# PWR_Sensor_Input.net
KiCad netlist of a schematic drawn in Altium Designer
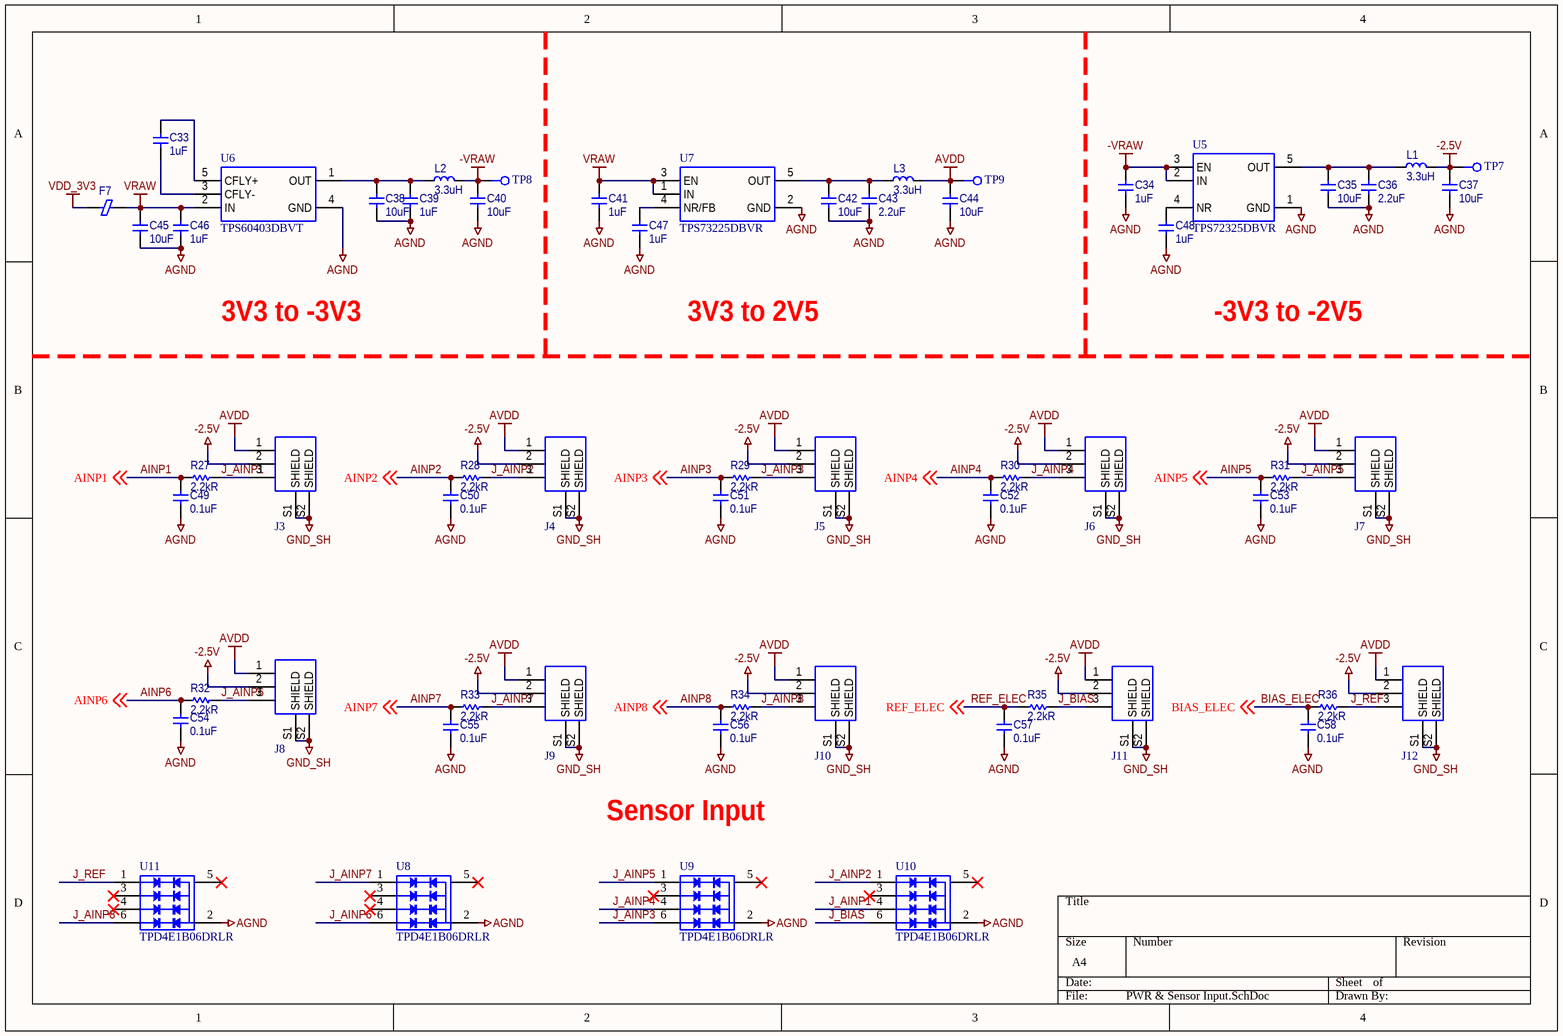
[diagram p0: PWR & Sensor Input.SchDoc]

(export (version "E")
  (design (tool "Eeschema 10.0.6"))
  (components
    (comp (ref "C33")
      (value "1uF")
      (footprint "C1005X04N")
      (description "CAP CER,1UF,10%,16V,X5R,0402,SMD")
      (fields
        (field (name "MANUFACTURER PART NUMBER") "EMK105BJ105KV-F")
        (field (name "MANUFACTURER") "Taiyo Yuden")
      )
      (libsource (lib "Database Library") (part "C_CAPN"))
    )
    (comp (ref "C34")
      (value "1uF")
      (footprint "C1005X04N")
      (description "CAP CER,1UF,10%,16V,X5R,0402,SMD")
      (fields
        (field (name "MANUFACTURER PART NUMBER") "EMK105BJ105KV-F")
        (field (name "MANUFACTURER") "Taiyo Yuden")
      )
      (libsource (lib "Database Library") (part "C_CAPN"))
    )
    (comp (ref "C35")
      (value "10uF")
      (footprint "C1608X06N")
      (description "CAP CER,10UF,20%,10V,X5R,0603,SMD")
      (fields
        (field (name "MANUFACTURER PART NUMBER") "LMK107BBJ106MAHT")
        (field (name "MANUFACTURER") "Taiyo Yuden")
      )
      (libsource (lib "Database Library") (part "C_CAPN"))
    )
    (comp (ref "C36")
      (value "2.2uF")
      (footprint "C1005X04N")
      (description "CAP CER,2.2UF,20%,25V,X5R,0402,SMD")
      (fields
        (field (name "MANUFACTURER PART NUMBER") "TMK105CBJ225MV-F")
        (field (name "MANUFACTURER") "Taiyo Yuden")
      )
      (libsource (lib "Database Library") (part "C_CAPN"))
    )
    (comp (ref "C37")
      (value "10uF")
      (footprint "C1608X06N")
      (description "CAP CER,10UF,20%,10V,X5R,0603,SMD")
      (fields
        (field (name "MANUFACTURER PART NUMBER") "LMK107BBJ106MAHT")
        (field (name "MANUFACTURER") "Taiyo Yuden")
      )
      (libsource (lib "Database Library") (part "C_CAPN"))
    )
    (comp (ref "C38")
      (value "10uF")
      (footprint "C1608X06N")
      (description "CAP CER,10UF,20%,10V,X5R,0603,SMD")
      (fields
        (field (name "MANUFACTURER PART NUMBER") "LMK107BBJ106MAHT")
        (field (name "MANUFACTURER") "Taiyo Yuden")
      )
      (libsource (lib "Database Library") (part "C_CAPN"))
    )
    (comp (ref "C39")
      (value "1uF")
      (footprint "C1005X04N")
      (description "CAP CER,1UF,10%,16V,X5R,0402,SMD")
      (fields
        (field (name "MANUFACTURER PART NUMBER") "EMK105BJ105KV-F")
        (field (name "MANUFACTURER") "Taiyo Yuden")
      )
      (libsource (lib "Database Library") (part "C_CAPN"))
    )
    (comp (ref "C40")
      (value "10uF")
      (footprint "C1608X06N")
      (description "CAP CER,10UF,20%,10V,X5R,0603,SMD")
      (fields
        (field (name "MANUFACTURER PART NUMBER") "LMK107BBJ106MAHT")
        (field (name "MANUFACTURER") "Taiyo Yuden")
      )
      (libsource (lib "Database Library") (part "C_CAPN"))
    )
    (comp (ref "C41")
      (value "1uF")
      (footprint "C1005X04N")
      (description "CAP CER,1UF,10%,16V,X5R,0402,SMD")
      (fields
        (field (name "MANUFACTURER PART NUMBER") "EMK105BJ105KV-F")
        (field (name "MANUFACTURER") "Taiyo Yuden")
      )
      (libsource (lib "Database Library") (part "C_CAPN"))
    )
    (comp (ref "C42")
      (value "10uF")
      (footprint "C1608X06N")
      (description "CAP CER,10UF,20%,10V,X5R,0603,SMD")
      (fields
        (field (name "MANUFACTURER PART NUMBER") "LMK107BBJ106MAHT")
        (field (name "MANUFACTURER") "Taiyo Yuden")
      )
      (libsource (lib "Database Library") (part "C_CAPN"))
    )
    (comp (ref "C43")
      (value "2.2uF")
      (footprint "C1005X04N")
      (description "CAP CER,2.2UF,20%,25V,X5R,0402,SMD")
      (fields
        (field (name "MANUFACTURER PART NUMBER") "TMK105CBJ225MV-F")
        (field (name "MANUFACTURER") "Taiyo Yuden")
      )
      (libsource (lib "Database Library") (part "C_CAPN"))
    )
    (comp (ref "C44")
      (value "10uF")
      (footprint "C1608X06N")
      (description "CAP CER,10UF,20%,10V,X5R,0603,SMD")
      (fields
        (field (name "MANUFACTURER PART NUMBER") "LMK107BBJ106MAHT")
        (field (name "MANUFACTURER") "Taiyo Yuden")
      )
      (libsource (lib "Database Library") (part "C_CAPN"))
    )
    (comp (ref "C45")
      (value "10uF")
      (footprint "C1608X06N")
      (description "CAP CER,10UF,20%,10V,X5R,0603,SMD")
      (fields
        (field (name "MANUFACTURER PART NUMBER") "LMK107BBJ106MAHT")
        (field (name "MANUFACTURER") "Taiyo Yuden")
      )
      (libsource (lib "Database Library") (part "C_CAPN"))
    )
    (comp (ref "C46")
      (value "1uF")
      (footprint "C1005X04N")
      (description "CAP CER,1UF,10%,16V,X5R,0402,SMD")
      (fields
        (field (name "MANUFACTURER PART NUMBER") "EMK105BJ105KV-F")
        (field (name "MANUFACTURER") "Taiyo Yuden")
      )
      (libsource (lib "Database Library") (part "C_CAPN"))
    )
    (comp (ref "C47")
      (value "1uF")
      (footprint "C1005X04N")
      (description "CAP CER,1UF,10%,16V,X5R,0402,SMD")
      (fields
        (field (name "MANUFACTURER PART NUMBER") "EMK105BJ105KV-F")
        (field (name "MANUFACTURER") "Taiyo Yuden")
      )
      (libsource (lib "Database Library") (part "C_CAPN"))
    )
    (comp (ref "C48")
      (value "1uF")
      (footprint "C1005X04N")
      (description "CAP CER,1UF,10%,16V,X5R,0402,SMD")
      (fields
        (field (name "MANUFACTURER PART NUMBER") "EMK105BJ105KV-F")
        (field (name "MANUFACTURER") "Taiyo Yuden")
      )
      (libsource (lib "Database Library") (part "C_CAPN"))
    )
    (comp (ref "C49")
      (value "0.1uF")
      (footprint "C1005X04N")
      (description "CAP CER,0.1UF,20%,25V,X5R,0402,SMD")
      (fields
        (field (name "MANUFACTURER PART NUMBER") "TMK105BJ104MV-F")
        (field (name "MANUFACTURER") "Taiyo Yuden")
      )
      (libsource (lib "Database Library") (part "C_CAPN"))
    )
    (comp (ref "C50")
      (value "0.1uF")
      (footprint "C1005X04N")
      (description "CAP CER,0.1UF,20%,25V,X5R,0402,SMD")
      (fields
        (field (name "MANUFACTURER PART NUMBER") "TMK105BJ104MV-F")
        (field (name "MANUFACTURER") "Taiyo Yuden")
      )
      (libsource (lib "Database Library") (part "C_CAPN"))
    )
    (comp (ref "C51")
      (value "0.1uF")
      (footprint "C1005X04N")
      (description "CAP CER,0.1UF,20%,25V,X5R,0402,SMD")
      (fields
        (field (name "MANUFACTURER PART NUMBER") "TMK105BJ104MV-F")
        (field (name "MANUFACTURER") "Taiyo Yuden")
      )
      (libsource (lib "Database Library") (part "C_CAPN"))
    )
    (comp (ref "C52")
      (value "0.1uF")
      (footprint "C1005X04N")
      (description "CAP CER,0.1UF,20%,25V,X5R,0402,SMD")
      (fields
        (field (name "MANUFACTURER PART NUMBER") "TMK105BJ104MV-F")
        (field (name "MANUFACTURER") "Taiyo Yuden")
      )
      (libsource (lib "Database Library") (part "C_CAPN"))
    )
    (comp (ref "C53")
      (value "0.1uF")
      (footprint "C1005X04N")
      (description "CAP CER,0.1UF,20%,25V,X5R,0402,SMD")
      (fields
        (field (name "MANUFACTURER PART NUMBER") "TMK105BJ104MV-F")
        (field (name "MANUFACTURER") "Taiyo Yuden")
      )
      (libsource (lib "Database Library") (part "C_CAPN"))
    )
    (comp (ref "C54")
      (value "0.1uF")
      (footprint "C1005X04N")
      (description "CAP CER,0.1UF,20%,25V,X5R,0402,SMD")
      (fields
        (field (name "MANUFACTURER PART NUMBER") "TMK105BJ104MV-F")
        (field (name "MANUFACTURER") "Taiyo Yuden")
      )
      (libsource (lib "Database Library") (part "C_CAPN"))
    )
    (comp (ref "C55")
      (value "0.1uF")
      (footprint "C1005X04N")
      (description "CAP CER,0.1UF,20%,25V,X5R,0402,SMD")
      (fields
        (field (name "MANUFACTURER PART NUMBER") "TMK105BJ104MV-F")
        (field (name "MANUFACTURER") "Taiyo Yuden")
      )
      (libsource (lib "Database Library") (part "C_CAPN"))
    )
    (comp (ref "C56")
      (value "0.1uF")
      (footprint "C1005X04N")
      (description "CAP CER,0.1UF,20%,25V,X5R,0402,SMD")
      (fields
        (field (name "MANUFACTURER PART NUMBER") "TMK105BJ104MV-F")
        (field (name "MANUFACTURER") "Taiyo Yuden")
      )
      (libsource (lib "Database Library") (part "C_CAPN"))
    )
    (comp (ref "C57")
      (value "0.1uF")
      (footprint "C1005X04N")
      (description "CAP CER,0.1UF,20%,25V,X5R,0402,SMD")
      (fields
        (field (name "MANUFACTURER PART NUMBER") "TMK105BJ104MV-F")
        (field (name "MANUFACTURER") "Taiyo Yuden")
      )
      (libsource (lib "Database Library") (part "C_CAPN"))
    )
    (comp (ref "C58")
      (value "0.1uF")
      (footprint "C1005X04N")
      (description "CAP CER,0.1UF,20%,25V,X5R,0402,SMD")
      (fields
        (field (name "MANUFACTURER PART NUMBER") "TMK105BJ104MV-F")
        (field (name "MANUFACTURER") "Taiyo Yuden")
      )
      (libsource (lib "Database Library") (part "C_CAPN"))
    )
    (comp (ref "F7")
      (value "120 Ohms @ 100MHz")
      (footprint "F3216X07N")
      (description "FERRITE BEAD,120 OHMS @ 100MHZ,0.0016R,3A,1206,SMD")
      (fields
        (field (name "MANUFACTURER PART NUMBER") "BLM31KN271BH1L")
        (field (name "MANUFACTURER") "Murata Electronics")
      )
      (libsource (lib "Database Library") (part "F_FERRITE_BEAD"))
    )
    (comp (ref "J3")
      (value "SM03B-SRSS-TB(LF)(SN)")
      (footprint "JST_SM03B-SRSS-TB(LF)(SN)")
      (description "CONN HEADER SMD R/A 3POS 1MM")
      (fields (field (name "MANUFACTURER") "JST Sales America Inc."))
      (libsource (lib "DungMV") (part "SM03B-SRSS-TB(LF)(SN)"))
    )
    (comp (ref "J4")
      (value "SM03B-SRSS-TB(LF)(SN)")
      (footprint "JST_SM03B-SRSS-TB(LF)(SN)")
      (description "CONN HEADER SMD R/A 3POS 1MM")
      (fields (field (name "MANUFACTURER") "JST Sales America Inc."))
      (libsource (lib "DungMV") (part "SM03B-SRSS-TB(LF)(SN)"))
    )
    (comp (ref "J5")
      (value "SM03B-SRSS-TB(LF)(SN)")
      (footprint "JST_SM03B-SRSS-TB(LF)(SN)")
      (description "CONN HEADER SMD R/A 3POS 1MM")
      (fields (field (name "MANUFACTURER") "JST Sales America Inc."))
      (libsource (lib "DungMV") (part "SM03B-SRSS-TB(LF)(SN)"))
    )
    (comp (ref "J6")
      (value "SM03B-SRSS-TB(LF)(SN)")
      (footprint "JST_SM03B-SRSS-TB(LF)(SN)")
      (description "CONN HEADER SMD R/A 3POS 1MM")
      (fields (field (name "MANUFACTURER") "JST Sales America Inc."))
      (libsource (lib "DungMV") (part "SM03B-SRSS-TB(LF)(SN)"))
    )
    (comp (ref "J7")
      (value "SM03B-SRSS-TB(LF)(SN)")
      (footprint "JST_SM03B-SRSS-TB(LF)(SN)")
      (description "CONN HEADER SMD R/A 3POS 1MM")
      (fields (field (name "MANUFACTURER") "JST Sales America Inc."))
      (libsource (lib "DungMV") (part "SM03B-SRSS-TB(LF)(SN)"))
    )
    (comp (ref "J8")
      (value "SM03B-SRSS-TB(LF)(SN)")
      (footprint "JST_SM03B-SRSS-TB(LF)(SN)")
      (description "CONN HEADER SMD R/A 3POS 1MM")
      (fields (field (name "MANUFACTURER") "JST Sales America Inc."))
      (libsource (lib "DungMV") (part "SM03B-SRSS-TB(LF)(SN)"))
    )
    (comp (ref "J9")
      (value "SM03B-SRSS-TB(LF)(SN)")
      (footprint "JST_SM03B-SRSS-TB(LF)(SN)")
      (description "CONN HEADER SMD R/A 3POS 1MM")
      (fields (field (name "MANUFACTURER") "JST Sales America Inc."))
      (libsource (lib "DungMV") (part "SM03B-SRSS-TB(LF)(SN)"))
    )
    (comp (ref "J10")
      (value "SM03B-SRSS-TB(LF)(SN)")
      (footprint "JST_SM03B-SRSS-TB(LF)(SN)")
      (description "CONN HEADER SMD R/A 3POS 1MM")
      (fields (field (name "MANUFACTURER") "JST Sales America Inc."))
      (libsource (lib "DungMV") (part "SM03B-SRSS-TB(LF)(SN)"))
    )
    (comp (ref "J11")
      (value "SM03B-SRSS-TB(LF)(SN)")
      (footprint "JST_SM03B-SRSS-TB(LF)(SN)")
      (description "CONN HEADER SMD R/A 3POS 1MM")
      (fields (field (name "MANUFACTURER") "JST Sales America Inc."))
      (libsource (lib "DungMV") (part "SM03B-SRSS-TB(LF)(SN)"))
    )
    (comp (ref "J12")
      (value "SM03B-SRSS-TB(LF)(SN)")
      (footprint "JST_SM03B-SRSS-TB(LF)(SN)")
      (description "CONN HEADER SMD R/A 3POS 1MM")
      (fields (field (name "MANUFACTURER") "JST Sales America Inc."))
      (libsource (lib "DungMV") (part "SM03B-SRSS-TB(LF)(SN)"))
    )
    (comp (ref "L1")
      (value "3.3uH")
      (footprint "L1608X06N")
      (description "IND,3.3UH,20%,450MA,0.027R,0603,SMD")
      (fields
        (field (name "MANUFACTURER PART NUMBER") "MLZ1608N3R3LT000")
        (field (name "MANUFACTURER") "TDK Corporation")
      )
      (libsource (lib "Database Library") (part "L_IND_AIR"))
    )
    (comp (ref "L2")
      (value "3.3uH")
      (footprint "L1608X06N")
      (description "IND,3.3UH,20%,450MA,0.027R,0603,SMD")
      (fields
        (field (name "MANUFACTURER PART NUMBER") "MLZ1608N3R3LT000")
        (field (name "MANUFACTURER") "TDK Corporation")
      )
      (libsource (lib "Database Library") (part "L_IND_AIR"))
    )
    (comp (ref "L3")
      (value "3.3uH")
      (footprint "L1608X06N")
      (description "IND,3.3UH,20%,450MA,0.027R,0603,SMD")
      (fields
        (field (name "MANUFACTURER PART NUMBER") "MLZ1608N3R3LT000")
        (field (name "MANUFACTURER") "TDK Corporation")
      )
      (libsource (lib "Database Library") (part "L_IND_AIR"))
    )
    (comp (ref "R27")
      (value "2.2kR")
      (footprint "R1005X04N")
      (description "RES,2.2KR,1%,62.5MW,0402,SMD")
      (fields
        (field (name "MANUFACTURER PART NUMBER") "RC0402FR-072K2L")
        (field (name "MANUFACTURER") "Yageo")
      )
      (libsource (lib "Database Library") (part "R_RES"))
    )
    (comp (ref "R28")
      (value "2.2kR")
      (footprint "R1005X04N")
      (description "RES,2.2KR,1%,62.5MW,0402,SMD")
      (fields
        (field (name "MANUFACTURER PART NUMBER") "RC0402FR-072K2L")
        (field (name "MANUFACTURER") "Yageo")
      )
      (libsource (lib "Database Library") (part "R_RES"))
    )
    (comp (ref "R29")
      (value "2.2kR")
      (footprint "R1005X04N")
      (description "RES,2.2KR,1%,62.5MW,0402,SMD")
      (fields
        (field (name "MANUFACTURER PART NUMBER") "RC0402FR-072K2L")
        (field (name "MANUFACTURER") "Yageo")
      )
      (libsource (lib "Database Library") (part "R_RES"))
    )
    (comp (ref "R30")
      (value "2.2kR")
      (footprint "R1005X04N")
      (description "RES,2.2KR,1%,62.5MW,0402,SMD")
      (fields
        (field (name "MANUFACTURER PART NUMBER") "RC0402FR-072K2L")
        (field (name "MANUFACTURER") "Yageo")
      )
      (libsource (lib "Database Library") (part "R_RES"))
    )
    (comp (ref "R31")
      (value "2.2kR")
      (footprint "R1005X04N")
      (description "RES,2.2KR,1%,62.5MW,0402,SMD")
      (fields
        (field (name "MANUFACTURER PART NUMBER") "RC0402FR-072K2L")
        (field (name "MANUFACTURER") "Yageo")
      )
      (libsource (lib "Database Library") (part "R_RES"))
    )
    (comp (ref "R32")
      (value "2.2kR")
      (footprint "R1005X04N")
      (description "RES,2.2KR,1%,62.5MW,0402,SMD")
      (fields
        (field (name "MANUFACTURER PART NUMBER") "RC0402FR-072K2L")
        (field (name "MANUFACTURER") "Yageo")
      )
      (libsource (lib "Database Library") (part "R_RES"))
    )
    (comp (ref "R33")
      (value "2.2kR")
      (footprint "R1005X04N")
      (description "RES,2.2KR,1%,62.5MW,0402,SMD")
      (fields
        (field (name "MANUFACTURER PART NUMBER") "RC0402FR-072K2L")
        (field (name "MANUFACTURER") "Yageo")
      )
      (libsource (lib "Database Library") (part "R_RES"))
    )
    (comp (ref "R34")
      (value "2.2kR")
      (footprint "R1005X04N")
      (description "RES,2.2KR,1%,62.5MW,0402,SMD")
      (fields
        (field (name "MANUFACTURER PART NUMBER") "RC0402FR-072K2L")
        (field (name "MANUFACTURER") "Yageo")
      )
      (libsource (lib "Database Library") (part "R_RES"))
    )
    (comp (ref "R35")
      (value "2.2kR")
      (footprint "R1005X04N")
      (description "RES,2.2KR,1%,62.5MW,0402,SMD")
      (fields
        (field (name "MANUFACTURER PART NUMBER") "RC0402FR-072K2L")
        (field (name "MANUFACTURER") "Yageo")
      )
      (libsource (lib "Database Library") (part "R_RES"))
    )
    (comp (ref "R36")
      (value "2.2kR")
      (footprint "R1005X04N")
      (description "RES,2.2KR,1%,62.5MW,0402,SMD")
      (fields
        (field (name "MANUFACTURER PART NUMBER") "RC0402FR-072K2L")
        (field (name "MANUFACTURER") "Yageo")
      )
      (libsource (lib "Database Library") (part "R_RES"))
    )
    (comp (ref "TP7")
      (value "TP_25MILC")
      (footprint "TESTPOINT_1MM")
      (description "Test Point 25mil")
      (libsource (lib "DungMV") (part "TP_25MILC"))
    )
    (comp (ref "TP8")
      (value "TP_25MILC")
      (footprint "TESTPOINT_1MM")
      (description "Test Point 25mil")
      (libsource (lib "DungMV") (part "TP_25MILC"))
    )
    (comp (ref "TP9")
      (value "TP_25MILC")
      (footprint "TESTPOINT_1MM")
      (description "Test Point 25mil")
      (libsource (lib "DungMV") (part "TP_25MILC"))
    )
    (comp (ref "U5")
      (value "TPS72325DBVR")
      (footprint "SOT23-5")
      (description "IC REG LIN -2.5V 200MA SOT23-5")
      (fields (field (name "MANUFACTURER") "Texas Instruments"))
      (libsource (lib "DungMV") (part "TPS72325DBVR"))
    )
    (comp (ref "U6")
      (value "TPS60403DBVT")
      (footprint "SOT23-5")
      (description "TPS60403 60MA CHARGE PUMP VOLTAG")
      (fields (field (name "MANUFACTURER") "Texas Instruments"))
      (libsource (lib "DungMV") (part "TPS60403DBVT"))
    )
    (comp (ref "U7")
      (value "TPS73225DBVR")
      (footprint "SOT23-5")
      (description "IC REG LINEAR 2.5V 250MA SOT23-5")
      (fields (field (name "MANUFACTURER") "Texas Instruments"))
      (libsource (lib "DungMV") (part "TPS73225DBVR"))
    )
    (comp (ref "U8")
      (value "TPD4E1B06DRLR")
      (footprint "SOT-563")
      (description "TVS DIODE 5.5VWM 14.5VC 6SOT")
      (fields (field (name "MANUFACTURER") "Texas Instruments"))
      (libsource (lib "DungMV") (part "TPD4E1B06DRLR"))
    )
    (comp (ref "U9")
      (value "TPD4E1B06DRLR")
      (footprint "SOT-563")
      (description "TVS DIODE 5.5VWM 14.5VC 6SOT")
      (fields (field (name "MANUFACTURER") "Texas Instruments"))
      (libsource (lib "DungMV") (part "TPD4E1B06DRLR"))
    )
    (comp (ref "U10")
      (value "TPD4E1B06DRLR")
      (footprint "SOT-563")
      (description "TVS DIODE 5.5VWM 14.5VC 6SOT")
      (fields (field (name "MANUFACTURER") "Texas Instruments"))
      (libsource (lib "DungMV") (part "TPD4E1B06DRLR"))
    )
    (comp (ref "U11")
      (value "TPD4E1B06DRLR")
      (footprint "SOT-563")
      (description "TVS DIODE 5.5VWM 14.5VC 6SOT")
      (fields (field (name "MANUFACTURER") "Texas Instruments"))
      (libsource (lib "DungMV") (part "TPD4E1B06DRLR"))
    )
  )
  (nets
    (net (code "1") (name "-2.5V") (class "Default")
      (node (ref "C37") (pin "2") (pinfunction "2_2") (pintype "passive"))
      (node (ref "J10") (pin "2") (pinfunction "2_2") (pintype "passive"))
      (node (ref "J11") (pin "2") (pinfunction "2_2") (pintype "passive"))
      (node (ref "J12") (pin "2") (pinfunction "2_2") (pintype "passive"))
      (node (ref "J3") (pin "2") (pinfunction "2_2") (pintype "passive"))
      (node (ref "J4") (pin "2") (pinfunction "2_2") (pintype "passive"))
      (node (ref "J5") (pin "2") (pinfunction "2_2") (pintype "passive"))
      (node (ref "J6") (pin "2") (pinfunction "2_2") (pintype "passive"))
      (node (ref "J7") (pin "2") (pinfunction "2_2") (pintype "passive"))
      (node (ref "J8") (pin "2") (pinfunction "2_2") (pintype "passive"))
      (node (ref "J9") (pin "2") (pinfunction "2_2") (pintype "passive"))
      (node (ref "L1") (pin "2") (pinfunction "2_2") (pintype "passive"))
      (node (ref "TP7") (pin "1") (pinfunction "1_1") (pintype "passive"))
    )
    (net (code "2") (name "-VRAW") (class "Default")
      (node (ref "C34") (pin "1") (pinfunction "1_1") (pintype "passive"))
      (node (ref "C40") (pin "2") (pinfunction "2_2") (pintype "passive"))
      (node (ref "L2") (pin "2") (pinfunction "2_2") (pintype "passive"))
      (node (ref "TP8") (pin "1") (pinfunction "1_1") (pintype "passive"))
      (node (ref "U5") (pin "2") (pinfunction "IN_2") (pintype "passive"))
      (node (ref "U5") (pin "3") (pinfunction "EN_3") (pintype "passive"))
    )
    (net (code "3") (name "/J_AINP1") (class "Default")
      (node (ref "J3") (pin "3") (pinfunction "3_3") (pintype "passive"))
      (node (ref "R27") (pin "2") (pinfunction "2_2") (pintype "passive"))
      (node (ref "U10") (pin "4") (pinfunction "IO3_4") (pintype "passive"))
    )
    (net (code "4") (name "/J_AINP2") (class "Default")
      (node (ref "J4") (pin "3") (pinfunction "3_3") (pintype "passive"))
      (node (ref "R28") (pin "2") (pinfunction "2_2") (pintype "passive"))
      (node (ref "U10") (pin "1") (pinfunction "IO1_1") (pintype "passive"))
    )
    (net (code "5") (name "/J_AINP3") (class "Default")
      (node (ref "J5") (pin "3") (pinfunction "3_3") (pintype "passive"))
      (node (ref "R29") (pin "2") (pinfunction "2_2") (pintype "passive"))
      (node (ref "U9") (pin "6") (pinfunction "IO4_6") (pintype "power_in"))
    )
    (net (code "6") (name "/J_AINP4") (class "Default")
      (node (ref "J6") (pin "3") (pinfunction "3_3") (pintype "passive"))
      (node (ref "R30") (pin "2") (pinfunction "2_2") (pintype "passive"))
      (node (ref "U9") (pin "4") (pinfunction "IO3_4") (pintype "passive"))
    )
    (net (code "7") (name "/J_AINP5") (class "Default")
      (node (ref "J7") (pin "3") (pinfunction "3_3") (pintype "passive"))
      (node (ref "R31") (pin "2") (pinfunction "2_2") (pintype "passive"))
      (node (ref "U9") (pin "1") (pinfunction "IO1_1") (pintype "passive"))
    )
    (net (code "8") (name "/J_AINP6") (class "Default")
      (node (ref "J8") (pin "3") (pinfunction "3_3") (pintype "passive"))
      (node (ref "R32") (pin "2") (pinfunction "2_2") (pintype "passive"))
      (node (ref "U8") (pin "6") (pinfunction "IO4_6") (pintype "power_in"))
    )
    (net (code "9") (name "/J_AINP7") (class "Default")
      (node (ref "J9") (pin "3") (pinfunction "3_3") (pintype "passive"))
      (node (ref "R33") (pin "2") (pinfunction "2_2") (pintype "passive"))
      (node (ref "U8") (pin "1") (pinfunction "IO1_1") (pintype "passive"))
    )
    (net (code "10") (name "/J_AINP8") (class "Default")
      (node (ref "J10") (pin "3") (pinfunction "3_3") (pintype "passive"))
      (node (ref "R34") (pin "2") (pinfunction "2_2") (pintype "passive"))
      (node (ref "U11") (pin "6") (pinfunction "IO4_6") (pintype "power_in"))
    )
    (net (code "11") (name "/J_BIAS") (class "Default")
      (node (ref "J11") (pin "3") (pinfunction "3_3") (pintype "passive"))
      (node (ref "R35") (pin "2") (pinfunction "2_2") (pintype "passive"))
      (node (ref "U10") (pin "6") (pinfunction "IO4_6") (pintype "power_in"))
    )
    (net (code "12") (name "/J_REF") (class "Default")
      (node (ref "J12") (pin "3") (pinfunction "3_3") (pintype "passive"))
      (node (ref "R36") (pin "2") (pinfunction "2_2") (pintype "passive"))
      (node (ref "U11") (pin "1") (pinfunction "IO1_1") (pintype "passive"))
    )
    (net (code "13") (name "AGND") (class "Default")
      (node (ref "C34") (pin "2") (pinfunction "2_2") (pintype "passive"))
      (node (ref "C35") (pin "1") (pinfunction "1_1") (pintype "passive"))
      (node (ref "C36") (pin "1") (pinfunction "1_1") (pintype "passive"))
      (node (ref "C37") (pin "1") (pinfunction "1_1") (pintype "passive"))
      (node (ref "C38") (pin "1") (pinfunction "1_1") (pintype "passive"))
      (node (ref "C39") (pin "2") (pinfunction "2_2") (pintype "passive"))
      (node (ref "C40") (pin "1") (pinfunction "1_1") (pintype "passive"))
      (node (ref "C41") (pin "2") (pinfunction "2_2") (pintype "passive"))
      (node (ref "C42") (pin "1") (pinfunction "1_1") (pintype "passive"))
      (node (ref "C43") (pin "1") (pinfunction "1_1") (pintype "passive"))
      (node (ref "C44") (pin "1") (pinfunction "1_1") (pintype "passive"))
      (node (ref "C45") (pin "1") (pinfunction "1_1") (pintype "passive"))
      (node (ref "C46") (pin "2") (pinfunction "2_2") (pintype "passive"))
      (node (ref "C47") (pin "2") (pinfunction "2_2") (pintype "passive"))
      (node (ref "C48") (pin "2") (pinfunction "2_2") (pintype "passive"))
      (node (ref "C49") (pin "1") (pinfunction "1_1") (pintype "passive"))
      (node (ref "C50") (pin "1") (pinfunction "1_1") (pintype "passive"))
      (node (ref "C51") (pin "1") (pinfunction "1_1") (pintype "passive"))
      (node (ref "C52") (pin "1") (pinfunction "1_1") (pintype "passive"))
      (node (ref "C53") (pin "1") (pinfunction "1_1") (pintype "passive"))
      (node (ref "C54") (pin "1") (pinfunction "1_1") (pintype "passive"))
      (node (ref "C55") (pin "1") (pinfunction "1_1") (pintype "passive"))
      (node (ref "C56") (pin "1") (pinfunction "1_1") (pintype "passive"))
      (node (ref "C57") (pin "1") (pinfunction "1_1") (pintype "passive"))
      (node (ref "C58") (pin "1") (pinfunction "1_1") (pintype "passive"))
      (node (ref "U10") (pin "2") (pinfunction "GND_2") (pintype "passive"))
      (node (ref "U11") (pin "2") (pinfunction "GND_2") (pintype "passive"))
      (node (ref "U5") (pin "1") (pinfunction "GND_1") (pintype "passive"))
      (node (ref "U6") (pin "4") (pinfunction "GND_4") (pintype "passive"))
      (node (ref "U7") (pin "2") (pinfunction "GND_2") (pintype "passive"))
      (node (ref "U8") (pin "2") (pinfunction "GND_2") (pintype "passive"))
      (node (ref "U9") (pin "2") (pinfunction "GND_2") (pintype "passive"))
    )
    (net (code "14") (name "AINP1") (class "Default")
      (node (ref "C49") (pin "2") (pinfunction "2_2") (pintype "passive"))
      (node (ref "R27") (pin "1") (pinfunction "1_1") (pintype "passive"))
    )
    (net (code "15") (name "AINP2") (class "Default")
      (node (ref "C50") (pin "2") (pinfunction "2_2") (pintype "passive"))
      (node (ref "R28") (pin "1") (pinfunction "1_1") (pintype "passive"))
    )
    (net (code "16") (name "AINP3") (class "Default")
      (node (ref "C51") (pin "2") (pinfunction "2_2") (pintype "passive"))
      (node (ref "R29") (pin "1") (pinfunction "1_1") (pintype "passive"))
    )
    (net (code "17") (name "AINP4") (class "Default")
      (node (ref "C52") (pin "2") (pinfunction "2_2") (pintype "passive"))
      (node (ref "R30") (pin "1") (pinfunction "1_1") (pintype "passive"))
    )
    (net (code "18") (name "AINP5") (class "Default")
      (node (ref "C53") (pin "2") (pinfunction "2_2") (pintype "passive"))
      (node (ref "R31") (pin "1") (pinfunction "1_1") (pintype "passive"))
    )
    (net (code "19") (name "AINP6") (class "Default")
      (node (ref "C54") (pin "2") (pinfunction "2_2") (pintype "passive"))
      (node (ref "R32") (pin "1") (pinfunction "1_1") (pintype "passive"))
    )
    (net (code "20") (name "AINP7") (class "Default")
      (node (ref "C55") (pin "2") (pinfunction "2_2") (pintype "passive"))
      (node (ref "R33") (pin "1") (pinfunction "1_1") (pintype "passive"))
    )
    (net (code "21") (name "AINP8") (class "Default")
      (node (ref "C56") (pin "2") (pinfunction "2_2") (pintype "passive"))
      (node (ref "R34") (pin "1") (pinfunction "1_1") (pintype "passive"))
    )
    (net (code "22") (name "AVDD") (class "Default")
      (node (ref "C44") (pin "2") (pinfunction "2_2") (pintype "passive"))
      (node (ref "J10") (pin "1") (pinfunction "1_1") (pintype "passive"))
      (node (ref "J11") (pin "1") (pinfunction "1_1") (pintype "passive"))
      (node (ref "J12") (pin "1") (pinfunction "1_1") (pintype "passive"))
      (node (ref "J3") (pin "1") (pinfunction "1_1") (pintype "passive"))
      (node (ref "J4") (pin "1") (pinfunction "1_1") (pintype "passive"))
      (node (ref "J5") (pin "1") (pinfunction "1_1") (pintype "passive"))
      (node (ref "J6") (pin "1") (pinfunction "1_1") (pintype "passive"))
      (node (ref "J7") (pin "1") (pinfunction "1_1") (pintype "passive"))
      (node (ref "J8") (pin "1") (pinfunction "1_1") (pintype "passive"))
      (node (ref "J9") (pin "1") (pinfunction "1_1") (pintype "passive"))
      (node (ref "L3") (pin "2") (pinfunction "2_2") (pintype "passive"))
      (node (ref "TP9") (pin "1") (pinfunction "1_1") (pintype "passive"))
    )
    (net (code "23") (name "BIAS_ELEC") (class "Default")
      (node (ref "C58") (pin "2") (pinfunction "2_2") (pintype "passive"))
      (node (ref "R36") (pin "1") (pinfunction "1_1") (pintype "passive"))
    )
    (net (code "24") (name "GND_SH") (class "Default")
      (node (ref "J10") (pin "S1") (pinfunction "SHIELD_S1") (pintype "passive"))
      (node (ref "J10") (pin "S2") (pinfunction "SHIELD_S2") (pintype "passive"))
      (node (ref "J11") (pin "S1") (pinfunction "SHIELD_S1") (pintype "passive"))
      (node (ref "J11") (pin "S2") (pinfunction "SHIELD_S2") (pintype "passive"))
      (node (ref "J12") (pin "S1") (pinfunction "SHIELD_S1") (pintype "passive"))
      (node (ref "J12") (pin "S2") (pinfunction "SHIELD_S2") (pintype "passive"))
      (node (ref "J3") (pin "S1") (pinfunction "SHIELD_S1") (pintype "passive"))
      (node (ref "J3") (pin "S2") (pinfunction "SHIELD_S2") (pintype "passive"))
      (node (ref "J4") (pin "S1") (pinfunction "SHIELD_S1") (pintype "passive"))
      (node (ref "J4") (pin "S2") (pinfunction "SHIELD_S2") (pintype "passive"))
      (node (ref "J5") (pin "S1") (pinfunction "SHIELD_S1") (pintype "passive"))
      (node (ref "J5") (pin "S2") (pinfunction "SHIELD_S2") (pintype "passive"))
      (node (ref "J6") (pin "S1") (pinfunction "SHIELD_S1") (pintype "passive"))
      (node (ref "J6") (pin "S2") (pinfunction "SHIELD_S2") (pintype "passive"))
      (node (ref "J7") (pin "S1") (pinfunction "SHIELD_S1") (pintype "passive"))
      (node (ref "J7") (pin "S2") (pinfunction "SHIELD_S2") (pintype "passive"))
      (node (ref "J8") (pin "S1") (pinfunction "SHIELD_S1") (pintype "passive"))
      (node (ref "J8") (pin "S2") (pinfunction "SHIELD_S2") (pintype "passive"))
      (node (ref "J9") (pin "S1") (pinfunction "SHIELD_S1") (pintype "passive"))
      (node (ref "J9") (pin "S2") (pinfunction "SHIELD_S2") (pintype "passive"))
    )
    (net (code "25") (name "Net-(U5-NR)") (class "Default")
      (node (ref "C48") (pin "1") (pinfunction "1_1") (pintype "passive"))
      (node (ref "U5") (pin "4") (pinfunction "NR_4") (pintype "passive"))
    )
    (net (code "26") (name "Net-(U5-OUT)") (class "Default")
      (node (ref "C35") (pin "2") (pinfunction "2_2") (pintype "passive"))
      (node (ref "C36") (pin "2") (pinfunction "2_2") (pintype "passive"))
      (node (ref "L1") (pin "1") (pinfunction "1_1") (pintype "passive"))
      (node (ref "U5") (pin "5") (pinfunction "OUT_5") (pintype "passive"))
    )
    (net (code "27") (name "Net-(U6-CFLY+)") (class "Default")
      (node (ref "C33") (pin "1") (pinfunction "1_1") (pintype "passive"))
      (node (ref "U6") (pin "5") (pinfunction "CFLY+_5") (pintype "passive"))
    )
    (net (code "28") (name "Net-(U6-CFLY-)") (class "Default")
      (node (ref "C33") (pin "2") (pinfunction "2_2") (pintype "passive"))
      (node (ref "U6") (pin "3") (pinfunction "CFLY-_3") (pintype "passive"))
    )
    (net (code "29") (name "Net-(U6-OUT)") (class "Default")
      (node (ref "C38") (pin "2") (pinfunction "2_2") (pintype "passive"))
      (node (ref "C39") (pin "1") (pinfunction "1_1") (pintype "passive"))
      (node (ref "L2") (pin "1") (pinfunction "1_1") (pintype "passive"))
      (node (ref "U6") (pin "1") (pinfunction "OUT_1") (pintype "passive"))
    )
    (net (code "30") (name "Net-(U7-NR{slash}FB)") (class "Default")
      (node (ref "C47") (pin "1") (pinfunction "1_1") (pintype "passive"))
      (node (ref "U7") (pin "4") (pinfunction "NR/FB_4") (pintype "passive"))
    )
    (net (code "31") (name "Net-(U7-OUT)") (class "Default")
      (node (ref "C42") (pin "2") (pinfunction "2_2") (pintype "passive"))
      (node (ref "C43") (pin "2") (pinfunction "2_2") (pintype "passive"))
      (node (ref "L3") (pin "1") (pinfunction "1_1") (pintype "passive"))
      (node (ref "U7") (pin "5") (pinfunction "OUT_5") (pintype "passive"))
    )
    (net (code "32") (name "REF_ELEC") (class "Default")
      (node (ref "C57") (pin "2") (pinfunction "2_2") (pintype "passive"))
      (node (ref "R35") (pin "1") (pinfunction "1_1") (pintype "passive"))
    )
    (net (code "33") (name "VDD_3V3") (class "Default")
      (node (ref "F7") (pin "1") (pinfunction "1_1") (pintype "passive"))
    )
    (net (code "34") (name "VRAW") (class "Default")
      (node (ref "C41") (pin "1") (pinfunction "1_1") (pintype "passive"))
      (node (ref "C45") (pin "2") (pinfunction "2_2") (pintype "passive"))
      (node (ref "C46") (pin "1") (pinfunction "1_1") (pintype "passive"))
      (node (ref "F7") (pin "2") (pinfunction "2_2") (pintype "passive"))
      (node (ref "U6") (pin "2") (pinfunction "IN_2") (pintype "passive"))
      (node (ref "U7") (pin "1") (pinfunction "IN_1") (pintype "passive"))
      (node (ref "U7") (pin "3") (pinfunction "EN_3") (pintype "passive"))
    )
    (net (code "35") (name "unconnected-(U8-IO2-Pad3)") (class "Default")
      (node (ref "U8") (pin "3") (pinfunction "IO2_3") (pintype "power_in+no_connect"))
    )
    (net (code "36") (name "unconnected-(U8-IO3-Pad4)") (class "Default")
      (node (ref "U8") (pin "4") (pinfunction "IO3_4") (pintype "passive+no_connect"))
    )
    (net (code "37") (name "unconnected-(U8-NC-Pad5)") (class "Default")
      (node (ref "U8") (pin "5") (pinfunction "NC_5") (pintype "passive+no_connect"))
    )
    (net (code "38") (name "unconnected-(U9-IO2-Pad3)") (class "Default")
      (node (ref "U9") (pin "3") (pinfunction "IO2_3") (pintype "power_in+no_connect"))
    )
    (net (code "39") (name "unconnected-(U9-NC-Pad5)") (class "Default")
      (node (ref "U9") (pin "5") (pinfunction "NC_5") (pintype "passive+no_connect"))
    )
    (net (code "40") (name "unconnected-(U10-IO2-Pad3)") (class "Default")
      (node (ref "U10") (pin "3") (pinfunction "IO2_3") (pintype "power_in+no_connect"))
    )
    (net (code "41") (name "unconnected-(U10-NC-Pad5)") (class "Default")
      (node (ref "U10") (pin "5") (pinfunction "NC_5") (pintype "passive+no_connect"))
    )
    (net (code "42") (name "unconnected-(U11-IO2-Pad3)") (class "Default")
      (node (ref "U11") (pin "3") (pinfunction "IO2_3") (pintype "power_in+no_connect"))
    )
    (net (code "43") (name "unconnected-(U11-IO3-Pad4)") (class "Default")
      (node (ref "U11") (pin "4") (pinfunction "IO3_4") (pintype "passive+no_connect"))
    )
    (net (code "44") (name "unconnected-(U11-NC-Pad5)") (class "Default")
      (node (ref "U11") (pin "5") (pinfunction "NC_5") (pintype "passive+no_connect"))
    )
  )
)
